# Board_MCU_v3.net
KiCad netlist of a schematic drawn in Altium Designer
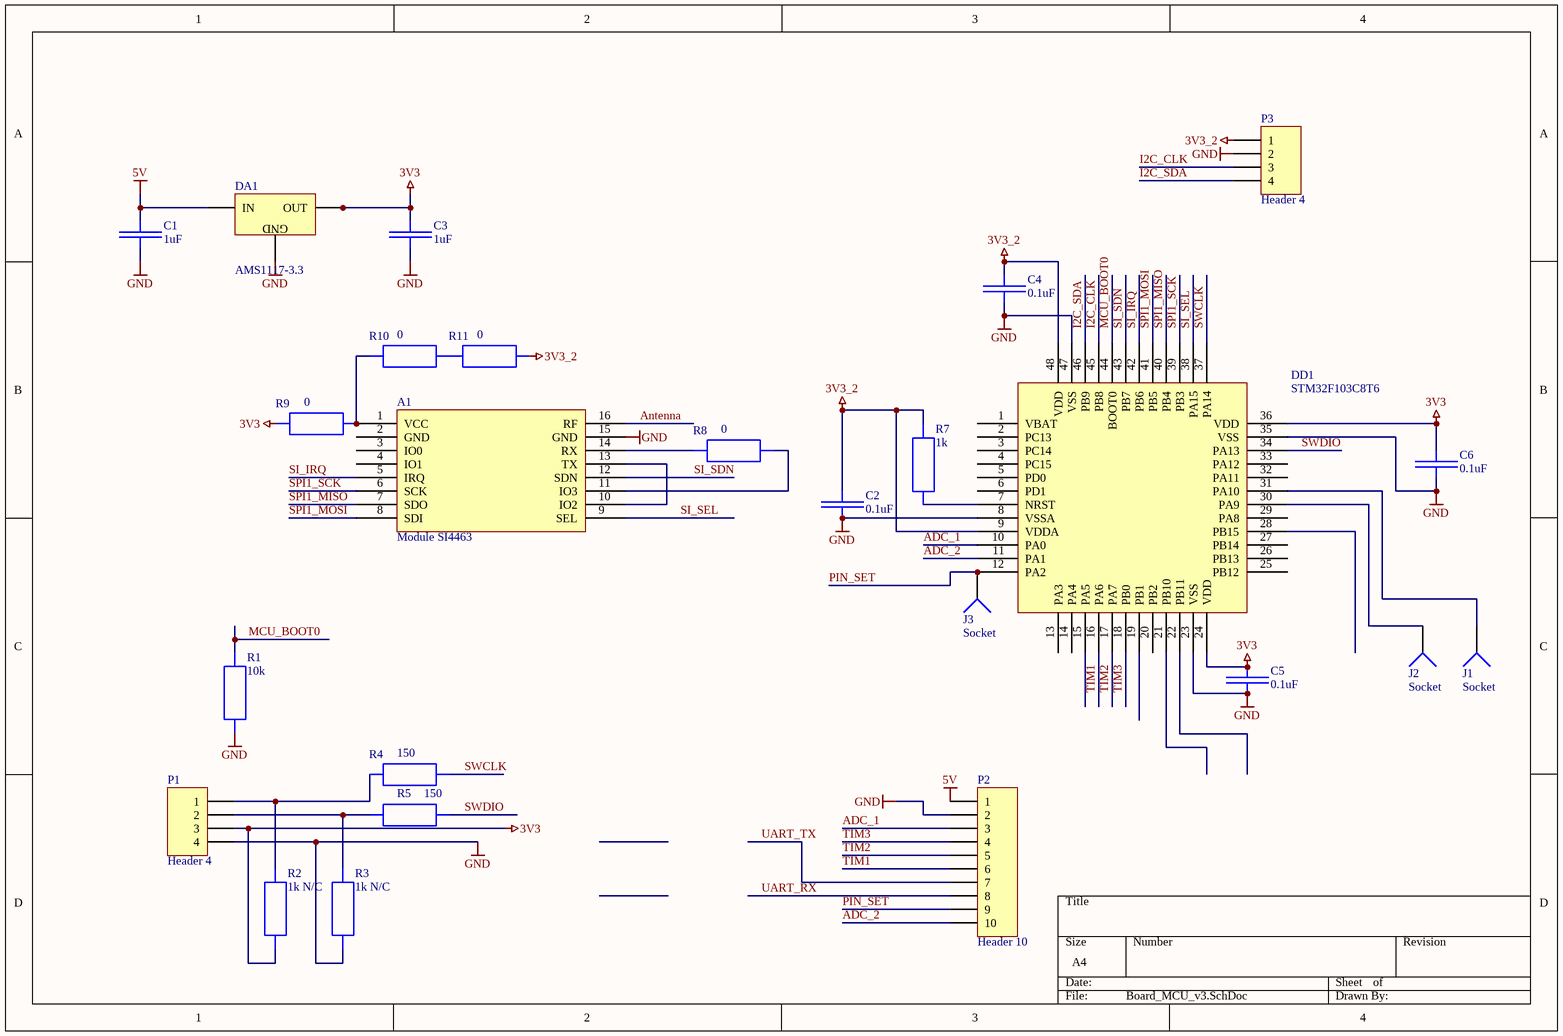
[diagram p0: Board_MCU_v3.SchDoc]

(export (version "E")
  (design (tool "Eeschema 10.0.6"))
  (components
    (comp (ref "A1")
      (value "Module SI4463")
      (footprint "MODULE_SI44663")
      (libsource (lib "Schlib1") (part "module_SI4463"))
    )
    (comp (ref "C1")
      (value "1uF")
      (footprint "0805cap")
      (fields (field (name "PART NUMBER") "Cap 0805"))
      (libsource (lib "PLAZ_PASSIVE") (part "C-0805"))
    )
    (comp (ref "C2")
      (value "0.1uF")
      (footprint "0805cap")
      (fields (field (name "PART NUMBER") "Cap 0805"))
      (libsource (lib "PLAZ_PASSIVE") (part "C-0805"))
    )
    (comp (ref "C3")
      (value "1uF")
      (footprint "0805cap")
      (fields (field (name "PART NUMBER") "Cap 0805"))
      (libsource (lib "PLAZ_PASSIVE") (part "C-0805"))
    )
    (comp (ref "C4")
      (value "0.1uF")
      (footprint "0805cap")
      (fields (field (name "PART NUMBER") "Cap 0805"))
      (libsource (lib "PLAZ_PASSIVE") (part "C-0805"))
    )
    (comp (ref "C5")
      (value "0.1uF")
      (footprint "0805cap")
      (fields (field (name "PART NUMBER") "Cap 0805"))
      (libsource (lib "PLAZ_PASSIVE") (part "C-0805"))
    )
    (comp (ref "C6")
      (value "0.1uF")
      (footprint "0805cap")
      (fields (field (name "PART NUMBER") "Cap 0805"))
      (libsource (lib "PLAZ_PASSIVE") (part "C-0805"))
    )
    (comp (ref "DA1")
      (value "AMS1117-3.3")
      (footprint "SOT-223")
      (description "LDO 3.3V 0.5A")
      (libsource (lib "Schlib1") (part "DA-AMS1117"))
    )
    (comp (ref "DD1")
      (value "STM32F103C8T6")
      (footprint "STM32L151C")
      (description "LQFP48")
      (libsource (lib "Schlib1") (part "STM32F103C8T6"))
    )
    (comp (ref "J1")
      (value "Socket")
      (footprint "PIN1")
      (fields (field (name "PUBLISHER") "Altium Limited"))
      (libsource (lib "Miscellaneous Connectors") (part "Socket"))
    )
    (comp (ref "J2")
      (value "Socket")
      (footprint "PIN1")
      (fields (field (name "PUBLISHER") "Altium Limited"))
      (libsource (lib "Miscellaneous Connectors") (part "Socket"))
    )
    (comp (ref "J3")
      (value "Socket")
      (footprint "PIN1")
      (fields (field (name "PUBLISHER") "Altium Limited"))
      (libsource (lib "Miscellaneous Connectors") (part "Socket"))
    )
    (comp (ref "P1")
      (value "Header 4")
      (footprint "HDR1X4")
      (description "Header, 4-Pin")
      (fields (field (name "PUBLISHER") "Altium Limited"))
      (libsource (lib "") (part "Header 4_1"))
    )
    (comp (ref "P2")
      (value "Header 10")
      (footprint "HDR1X10")
      (description "Header, 10-Pin")
      (fields (field (name "PUBLISHER") "Altium Limited"))
      (libsource (lib "Miscellaneous Connectors") (part "Header 10"))
    )
    (comp (ref "P3")
      (value "Header 4")
      (footprint "HDR1X4")
      (description "Header, 4-Pin")
      (fields (field (name "PUBLISHER") "Altium Limited"))
      (libsource (lib "Miscellaneous Connectors") (part "Header 4"))
    )
    (comp (ref "R1")
      (value "10k")
      (footprint "0805res")
      (fields (field (name "PART NUMBER") "Res 0805") (field (name "TOLERANCE") "1%"))
      (libsource (lib "PLAZ_PASSIVE") (part "R-0805"))
    )
    (comp (ref "R2")
      (value "1k N/C")
      (footprint "0805res")
      (fields (field (name "PART NUMBER") "Res 0805") (field (name "TOLERANCE") "1%"))
      (libsource (lib "PLAZ_PASSIVE") (part "R-0805"))
    )
    (comp (ref "R3")
      (value "1k N/C")
      (footprint "0805res")
      (fields (field (name "PART NUMBER") "Res 0805") (field (name "TOLERANCE") "1%"))
      (libsource (lib "PLAZ_PASSIVE") (part "R-0805"))
    )
    (comp (ref "R4")
      (value "150")
      (footprint "0805res")
      (fields (field (name "PART NUMBER") "Res 0805") (field (name "TOLERANCE") "1%"))
      (libsource (lib "PLAZ_PASSIVE") (part "R-0805"))
    )
    (comp (ref "R5")
      (value "150")
      (footprint "0805res")
      (fields (field (name "PART NUMBER") "Res 0805") (field (name "TOLERANCE") "1%"))
      (libsource (lib "PLAZ_PASSIVE") (part "R-0805"))
    )
    (comp (ref "R7")
      (value "1k")
      (footprint "0805res")
      (fields (field (name "PART NUMBER") "Res 0805") (field (name "TOLERANCE") "1%"))
      (libsource (lib "PLAZ_PASSIVE") (part "R-0805"))
    )
    (comp (ref "R8")
      (value "0")
      (footprint "0805res")
      (fields (field (name "PART NUMBER") "Res 0805") (field (name "TOLERANCE") "1%"))
      (libsource (lib "PLAZ_PASSIVE") (part "R-0805"))
    )
    (comp (ref "R9")
      (value "0")
      (footprint "0805res")
      (fields (field (name "PART NUMBER") "Res 0805") (field (name "TOLERANCE") "1%"))
      (libsource (lib "PLAZ_PASSIVE") (part "R-0805"))
    )
    (comp (ref "R10")
      (value "0")
      (footprint "0805res")
      (fields (field (name "PART NUMBER") "Res 0805") (field (name "TOLERANCE") "1%"))
      (libsource (lib "PLAZ_PASSIVE") (part "R-0805"))
    )
    (comp (ref "R11")
      (value "0")
      (footprint "0805res")
      (fields (field (name "PART NUMBER") "Res 0805") (field (name "TOLERANCE") "1%"))
      (libsource (lib "PLAZ_PASSIVE") (part "R-0805"))
    )
  )
  (nets
    (net (code "1") (name "/ADC_1") (class "Default")
      (node (ref "DD1") (pin "10") (pinfunction "PA0_10") (pintype "passive"))
      (node (ref "P2") (pin "3") (pinfunction "3_3") (pintype "passive"))
    )
    (net (code "2") (name "/ADC_2") (class "Default")
      (node (ref "DD1") (pin "11") (pinfunction "PA1_11") (pintype "passive"))
      (node (ref "P2") (pin "10") (pinfunction "10_10") (pintype "passive"))
    )
    (net (code "3") (name "/Antenna") (class "Default")
      (node (ref "A1") (pin "16") (pinfunction "RF_16") (pintype "passive"))
    )
    (net (code "4") (name "/I2C_CLK") (class "Default")
      (node (ref "DD1") (pin "45") (pinfunction "PB8_45") (pintype "passive"))
      (node (ref "P3") (pin "3") (pinfunction "3_3") (pintype "passive"))
    )
    (net (code "5") (name "/I2C_SDA") (class "Default")
      (node (ref "DD1") (pin "46") (pinfunction "PB9_46") (pintype "passive"))
      (node (ref "P3") (pin "4") (pinfunction "4_4") (pintype "passive"))
    )
    (net (code "6") (name "/MCU_BOOT0") (class "Default")
      (node (ref "DD1") (pin "44") (pinfunction "BOOT0_44") (pintype "passive"))
      (node (ref "R1") (pin "1") (pintype "passive"))
    )
    (net (code "7") (name "/PIN_SET") (class "Default")
      (node (ref "DD1") (pin "12") (pinfunction "PA2_12") (pintype "passive"))
      (node (ref "J3") (pin "1") (pinfunction "1_1") (pintype "passive"))
      (node (ref "P2") (pin "9") (pinfunction "9_9") (pintype "passive"))
    )
    (net (code "8") (name "/SI_IRQ") (class "Default")
      (node (ref "A1") (pin "5") (pinfunction "IRQ_5") (pintype "passive"))
      (node (ref "DD1") (pin "42") (pinfunction "PB6_42") (pintype "passive"))
    )
    (net (code "9") (name "/SI_SDN") (class "Default")
      (node (ref "A1") (pin "12") (pinfunction "SDN_12") (pintype "passive"))
      (node (ref "DD1") (pin "43") (pinfunction "PB7_43") (pintype "passive"))
    )
    (net (code "10") (name "/SI_SEL") (class "Default")
      (node (ref "A1") (pin "9") (pinfunction "SEL_9") (pintype "passive"))
      (node (ref "DD1") (pin "38") (pinfunction "PA15_38") (pintype "passive"))
    )
    (net (code "11") (name "/SPI1_MISO") (class "Default")
      (node (ref "A1") (pin "7") (pinfunction "SDO_7") (pintype "passive"))
      (node (ref "DD1") (pin "40") (pinfunction "PB4_40") (pintype "passive"))
    )
    (net (code "12") (name "/SPI1_MOSI") (class "Default")
      (node (ref "A1") (pin "8") (pinfunction "SDI_8") (pintype "passive"))
      (node (ref "DD1") (pin "41") (pinfunction "PB5_41") (pintype "passive"))
    )
    (net (code "13") (name "/SPI1_SCK") (class "Default")
      (node (ref "A1") (pin "6") (pinfunction "SCK_6") (pintype "passive"))
      (node (ref "DD1") (pin "39") (pinfunction "PB3_39") (pintype "passive"))
    )
    (net (code "14") (name "/SWCLK") (class "Default")
      (node (ref "DD1") (pin "37") (pinfunction "PA14_37") (pintype "passive"))
      (node (ref "R4") (pin "1") (pintype "passive"))
    )
    (net (code "15") (name "/SWDIO") (class "Default")
      (node (ref "DD1") (pin "34") (pinfunction "PA13_34") (pintype "passive"))
      (node (ref "R5") (pin "1") (pintype "passive"))
    )
    (net (code "16") (name "/TIM1") (class "Default")
      (node (ref "DD1") (pin "16") (pinfunction "PA6_16") (pintype "passive"))
      (node (ref "P2") (pin "6") (pinfunction "6_6") (pintype "passive"))
    )
    (net (code "17") (name "/TIM2") (class "Default")
      (node (ref "DD1") (pin "17") (pinfunction "PA7_17") (pintype "passive"))
      (node (ref "P2") (pin "5") (pinfunction "5_5") (pintype "passive"))
    )
    (net (code "18") (name "/TIM3") (class "Default")
      (node (ref "DD1") (pin "18") (pinfunction "PB0_18") (pintype "passive"))
      (node (ref "P2") (pin "4") (pinfunction "4_4") (pintype "passive"))
    )
    (net (code "19") (name "/UART_RX") (class "Default")
      (node (ref "P2") (pin "8") (pinfunction "8_8") (pintype "passive"))
    )
    (net (code "20") (name "/UART_TX") (class "Default")
      (node (ref "P2") (pin "7") (pinfunction "7_7") (pintype "passive"))
    )
    (net (code "21") (name "3V3") (class "Default")
      (node (ref "C3") (pin "1") (pintype "passive"))
      (node (ref "C5") (pin "1") (pintype "passive"))
      (node (ref "C6") (pin "1") (pintype "passive"))
      (node (ref "DA1") (pin "2") (pinfunction "OUT_2") (pintype "passive"))
      (node (ref "DA1") (pin "4") (pinfunction "4_4") (pintype "passive"))
      (node (ref "DD1") (pin "24") (pinfunction "VDD_24") (pintype "passive"))
      (node (ref "DD1") (pin "36") (pinfunction "VDD_36") (pintype "passive"))
      (node (ref "P1") (pin "3") (pinfunction "3_3") (pintype "passive"))
      (node (ref "R2") (pin "2") (pintype "passive"))
      (node (ref "R9") (pin "1") (pintype "passive"))
    )
    (net (code "22") (name "3V3_2") (class "Default")
      (node (ref "C2") (pin "1") (pintype "passive"))
      (node (ref "C4") (pin "1") (pintype "passive"))
      (node (ref "DD1") (pin "48") (pinfunction "VDD_48") (pintype "passive"))
      (node (ref "DD1") (pin "9") (pinfunction "VDDA_9") (pintype "passive"))
      (node (ref "P3") (pin "1") (pinfunction "1_1") (pintype "passive"))
      (node (ref "R11") (pin "2") (pintype "passive"))
      (node (ref "R7") (pin "1") (pintype "passive"))
    )
    (net (code "23") (name "5V") (class "Default")
      (node (ref "C1") (pin "1") (pintype "passive"))
      (node (ref "DA1") (pin "3") (pinfunction "IN_3") (pintype "passive"))
      (node (ref "P2") (pin "1") (pinfunction "1_1") (pintype "passive"))
    )
    (net (code "24") (name "GND") (class "Default")
      (node (ref "A1") (pin "15") (pinfunction "GND_15") (pintype "passive"))
      (node (ref "C1") (pin "2") (pintype "passive"))
      (node (ref "C2") (pin "2") (pintype "passive"))
      (node (ref "C3") (pin "2") (pintype "passive"))
      (node (ref "C4") (pin "2") (pintype "passive"))
      (node (ref "C5") (pin "2") (pintype "passive"))
      (node (ref "C6") (pin "2") (pintype "passive"))
      (node (ref "DA1") (pin "1") (pinfunction "GND_1") (pintype "passive"))
      (node (ref "DD1") (pin "23") (pinfunction "VSS_23") (pintype "passive"))
      (node (ref "DD1") (pin "35") (pinfunction "VSS_35") (pintype "passive"))
      (node (ref "DD1") (pin "47") (pinfunction "VSS_47") (pintype "passive"))
      (node (ref "DD1") (pin "8") (pinfunction "VSSA_8") (pintype "passive"))
      (node (ref "P1") (pin "4") (pinfunction "4_4") (pintype "passive"))
      (node (ref "P2") (pin "2") (pinfunction "2_2") (pintype "passive"))
      (node (ref "P3") (pin "2") (pinfunction "2_2") (pintype "passive"))
      (node (ref "R1") (pin "2") (pintype "passive"))
      (node (ref "R3") (pin "2") (pintype "passive"))
    )
    (net (code "25") (name "Net-(A1-IO2)") (class "Default")
      (node (ref "A1") (pin "10") (pinfunction "IO2_10") (pintype "passive"))
      (node (ref "A1") (pin "13") (pinfunction "TX_13") (pintype "passive"))
    )
    (net (code "26") (name "Net-(A1-IO3)") (class "Default")
      (node (ref "A1") (pin "11") (pinfunction "IO3_11") (pintype "passive"))
      (node (ref "R8") (pin "2") (pintype "passive"))
    )
    (net (code "27") (name "Net-(A1-RX)") (class "Default")
      (node (ref "A1") (pin "14") (pinfunction "RX_14") (pintype "passive"))
      (node (ref "R8") (pin "1") (pintype "passive"))
    )
    (net (code "28") (name "Net-(A1-VCC)") (class "Default")
      (node (ref "A1") (pin "1") (pinfunction "VCC_1") (pintype "passive"))
      (node (ref "R10") (pin "1") (pintype "passive"))
      (node (ref "R9") (pin "2") (pintype "passive"))
    )
    (net (code "29") (name "Net-(DD1-NRST)") (class "Default")
      (node (ref "DD1") (pin "7") (pinfunction "NRST_7") (pintype "passive"))
      (node (ref "R7") (pin "2") (pintype "passive"))
    )
    (net (code "30") (name "Net-(DD1-PA9)") (class "Default")
      (node (ref "DD1") (pin "30") (pinfunction "PA9_30") (pintype "passive"))
      (node (ref "J2") (pin "1") (pinfunction "1_1") (pintype "passive"))
    )
    (net (code "31") (name "Net-(DD1-PA10)") (class "Default")
      (node (ref "DD1") (pin "31") (pinfunction "PA10_31") (pintype "passive"))
      (node (ref "J1") (pin "1") (pinfunction "1_1") (pintype "passive"))
    )
    (net (code "32") (name "Net-(P1-Pad1)") (class "Default")
      (node (ref "P1") (pin "1") (pinfunction "1_1") (pintype "passive"))
      (node (ref "R2") (pin "1") (pintype "passive"))
      (node (ref "R4") (pin "2") (pintype "passive"))
    )
    (net (code "33") (name "Net-(P1-Pad2)") (class "Default")
      (node (ref "P1") (pin "2") (pinfunction "2_2") (pintype "passive"))
      (node (ref "R3") (pin "1") (pintype "passive"))
      (node (ref "R5") (pin "2") (pintype "passive"))
    )
    (net (code "34") (name "Net-(R10-Pad2)") (class "Default")
      (node (ref "R10") (pin "2") (pintype "passive"))
      (node (ref "R11") (pin "1") (pintype "passive"))
    )
    (net (code "35") (name "unconnected-(A1-GND-Pad2)") (class "Default")
      (node (ref "A1") (pin "2") (pinfunction "GND_2") (pintype "passive"))
    )
    (net (code "36") (name "unconnected-(A1-IO0-Pad3)") (class "Default")
      (node (ref "A1") (pin "3") (pinfunction "IO0_3") (pintype "passive"))
    )
    (net (code "37") (name "unconnected-(A1-IO1-Pad4)") (class "Default")
      (node (ref "A1") (pin "4") (pinfunction "IO1_4") (pintype "passive"))
    )
    (net (code "38") (name "unconnected-(DD1-PA3-Pad13)") (class "Default")
      (node (ref "DD1") (pin "13") (pinfunction "PA3_13") (pintype "passive"))
    )
    (net (code "39") (name "unconnected-(DD1-PA4-Pad14)") (class "Default")
      (node (ref "DD1") (pin "14") (pinfunction "PA4_14") (pintype "passive"))
    )
    (net (code "40") (name "unconnected-(DD1-PA5-Pad15)") (class "Default")
      (node (ref "DD1") (pin "15") (pinfunction "PA5_15") (pintype "passive"))
    )
    (net (code "41") (name "unconnected-(DD1-PA8-Pad29)") (class "Default")
      (node (ref "DD1") (pin "29") (pinfunction "PA8_29") (pintype "passive"))
    )
    (net (code "42") (name "unconnected-(DD1-PA11-Pad32)") (class "Default")
      (node (ref "DD1") (pin "32") (pinfunction "PA11_32") (pintype "passive"))
    )
    (net (code "43") (name "unconnected-(DD1-PA12-Pad33)") (class "Default")
      (node (ref "DD1") (pin "33") (pinfunction "PA12_33") (pintype "passive"))
    )
    (net (code "44") (name "unconnected-(DD1-PB1-Pad19)") (class "Default")
      (node (ref "DD1") (pin "19") (pinfunction "PB1_19") (pintype "passive"))
    )
    (net (code "45") (name "unconnected-(DD1-PB2-Pad20)") (class "Default")
      (node (ref "DD1") (pin "20") (pinfunction "PB2_20") (pintype "passive"))
    )
    (net (code "46") (name "unconnected-(DD1-PB10-Pad21)") (class "Default")
      (node (ref "DD1") (pin "21") (pinfunction "PB10_21") (pintype "passive"))
    )
    (net (code "47") (name "unconnected-(DD1-PB11-Pad22)") (class "Default")
      (node (ref "DD1") (pin "22") (pinfunction "PB11_22") (pintype "passive"))
    )
    (net (code "48") (name "unconnected-(DD1-PB12-Pad25)") (class "Default")
      (node (ref "DD1") (pin "25") (pinfunction "PB12_25") (pintype "passive"))
    )
    (net (code "49") (name "unconnected-(DD1-PB13-Pad26)") (class "Default")
      (node (ref "DD1") (pin "26") (pinfunction "PB13_26") (pintype "passive"))
    )
    (net (code "50") (name "unconnected-(DD1-PB14-Pad27)") (class "Default")
      (node (ref "DD1") (pin "27") (pinfunction "PB14_27") (pintype "passive"))
    )
    (net (code "51") (name "unconnected-(DD1-PB15-Pad28)") (class "Default")
      (node (ref "DD1") (pin "28") (pinfunction "PB15_28") (pintype "passive"))
    )
    (net (code "52") (name "unconnected-(DD1-PC13-Pad2)") (class "Default")
      (node (ref "DD1") (pin "2") (pinfunction "PC13_2") (pintype "passive"))
    )
    (net (code "53") (name "unconnected-(DD1-PC14-Pad3)") (class "Default")
      (node (ref "DD1") (pin "3") (pinfunction "PC14_3") (pintype "passive"))
    )
    (net (code "54") (name "unconnected-(DD1-PC15-Pad4)") (class "Default")
      (node (ref "DD1") (pin "4") (pinfunction "PC15_4") (pintype "passive"))
    )
    (net (code "55") (name "unconnected-(DD1-PD0-Pad5)") (class "Default")
      (node (ref "DD1") (pin "5") (pinfunction "PD0_5") (pintype "passive"))
    )
    (net (code "56") (name "unconnected-(DD1-PD1-Pad6)") (class "Default")
      (node (ref "DD1") (pin "6") (pinfunction "PD1_6") (pintype "passive"))
    )
    (net (code "57") (name "unconnected-(DD1-VBAT-Pad1)") (class "Default")
      (node (ref "DD1") (pin "1") (pinfunction "VBAT_1") (pintype "passive"))
    )
  )
)
